# DC_Link.net
KiCad netlist of a schematic drawn in Altium Designer
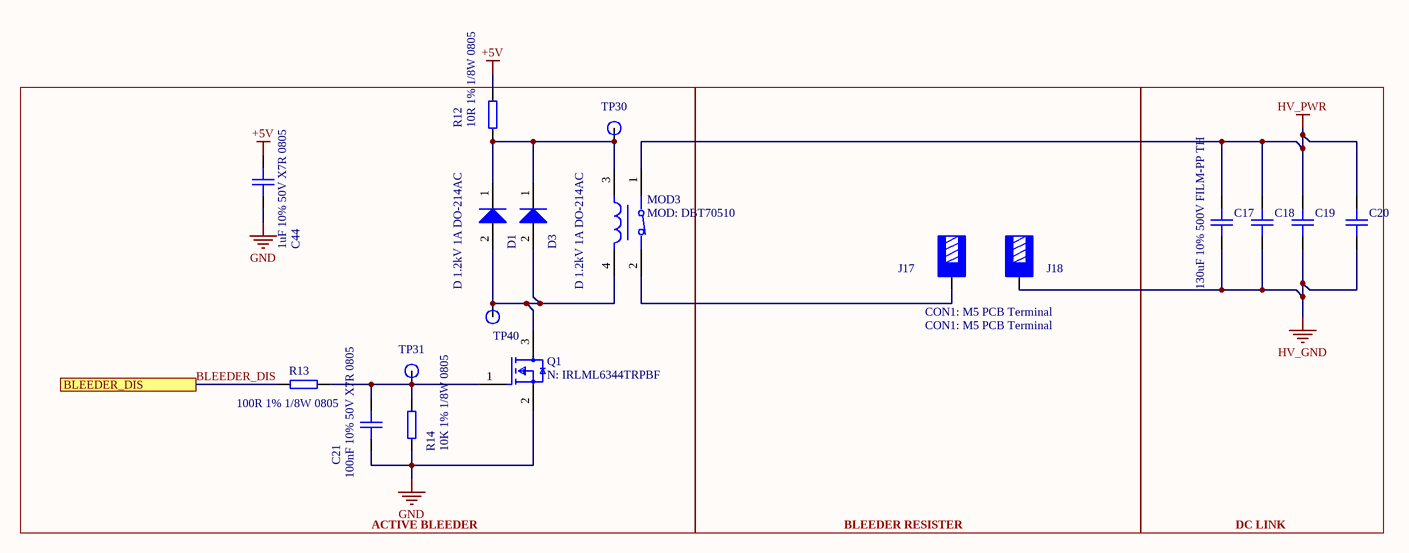
[diagram p0: DC_Link.SchDoc]

(export (version "E")
  (design (tool "Eeschema 10.0.6"))
  (components
    (comp (ref "C17")
      (value "130uF 10% 500V FILM-PP TH")
      (footprint "New footprint 1")
      (description "130 µF Film Capacitor 500V Polypropylene (PP), Metallized Radial - 4 Leads")
      (fields
        (field (name "MANUFACTURER") "KEMET")
        (field (name "MANUFACTURER PART NUMBER") "C4AQLBW6130A3NK")
      )
      (libsource (lib "EMEA- E-Tech Racing- I'Escola d'Enginyeria de Barcelona Est") (part "Copy of Capacitor_Non-Polarized"))
    )
    (comp (ref "C18")
      (value "130uF 10% 500V FILM-PP TH")
      (footprint "New footprint 1")
      (description "130 µF Film Capacitor 500V Polypropylene (PP), Metallized Radial - 4 Leads")
      (fields
        (field (name "MANUFACTURER") "KEMET")
        (field (name "MANUFACTURER PART NUMBER") "C4AQLBW6130A3NK")
      )
      (libsource (lib "EMEA- E-Tech Racing- I'Escola d'Enginyeria de Barcelona Est") (part "Copy of Capacitor_Non-Polarized"))
    )
    (comp (ref "C19")
      (value "130uF 10% 500V FILM-PP TH")
      (footprint "New footprint 1")
      (description "130 µF Film Capacitor 500V Polypropylene (PP), Metallized Radial - 4 Leads")
      (fields
        (field (name "MANUFACTURER") "KEMET")
        (field (name "MANUFACTURER PART NUMBER") "C4AQLBW6130A3NK")
      )
      (libsource (lib "EMEA- E-Tech Racing- I'Escola d'Enginyeria de Barcelona Est") (part "Copy of Capacitor_Non-Polarized"))
    )
    (comp (ref "C20")
      (value "130uF 10% 500V FILM-PP TH")
      (footprint "New footprint 1")
      (description "130 µF Film Capacitor 500V Polypropylene (PP), Metallized Radial - 4 Leads")
      (fields
        (field (name "MANUFACTURER") "KEMET")
        (field (name "MANUFACTURER PART NUMBER") "C4AQLBW6130A3NK")
      )
      (libsource (lib "EMEA- E-Tech Racing- I'Escola d'Enginyeria de Barcelona Est") (part "Copy of Capacitor_Non-Polarized"))
    )
    (comp (ref "C21")
      (value "100nF 10% 50V X7R 0805")
      (footprint "CAPC2012X10N")
      (description "Multilayer Ceramic Capacitors MLCC - SMD/SMT 50V 0.1uF X7R 0805 10%")
      (fields
        (field (name "MANUFACTURER") "Stackpole Electronics")
        (field (name "MANUFACTURER PART NUMBER") "CML0805X7R104KT50V")
      )
      (libsource (lib "EMEA- E-Tech Racing- I'Escola d'Enginyeria de Barcelona Est") (part "100nF 10% 50V X7R 0805-Symbol-1"))
    )
    (comp (ref "C44")
      (value "1uF 10% 50V X7R 0805")
      (footprint "CAPC2012X10N")
      (fields
        (field (name "MANUFACTURER PART NUMBER") "C2012X7R1H105K125AB")
        (field (name "MANUFACTURER") "TDK")
      )
      (libsource (lib "EMEA- E-Tech Racing- I'Escola d'Enginyeria de Barcelona Est") (part "68pF 10 630V C0G 0805"))
    )
    (comp (ref "D1")
      (value "D 1.2kV 1A DO-214AC")
      (footprint "FP-95400-MFG")
      (description "Rectifier Diode, 1 Phase, 1 Element, 1A, 1000V V(RRM), Silicon, DO-214AC")
      (fields (field (name "VOLTAGE") "1kV") (field (name "MANUFACTURER") "Vishay"))
      (libsource (lib "EMEA- E-Tech Racing- I'Escola d'Enginyeria de Barcelona Est") (part "SD 1.2kV 1A"))
    )
    (comp (ref "D3")
      (value "D 1.2kV 1A DO-214AC")
      (footprint "FP-95400-MFG")
      (description "Rectifier Diode, 1 Phase, 1 Element, 1A, 1000V V(RRM), Silicon, DO-214AC")
      (fields (field (name "VOLTAGE") "1kV") (field (name "MANUFACTURER") "Vishay"))
      (libsource (lib "EMEA- E-Tech Racing- I'Escola d'Enginyeria de Barcelona Est") (part "SD 1.2kV 1A"))
    )
    (comp (ref "J17")
      (value "CON1: M5 PCB Terminal")
      (footprint "CON1: M5 PCB Terminal-Footprint-1")
      (fields (field (name "MANUFACTURER") "Lab") (field (name "MANUFACTURER PART NUMBER") "M5 PCB Terminal"))
      (libsource (lib "EMEA- E-Tech Racing- I'Escola d'Enginyeria de Barcelona Est") (part "CON1{colon} M5 PCB Terminal-Symbol-1"))
    )
    (comp (ref "J18")
      (value "CON1: M5 PCB Terminal")
      (footprint "CON1: M5 PCB Terminal-Footprint-1")
      (fields (field (name "MANUFACTURER") "Lab") (field (name "MANUFACTURER PART NUMBER") "M5 PCB Terminal"))
      (libsource (lib "EMEA- E-Tech Racing- I'Escola d'Enginyeria de Barcelona Est") (part "CON1{colon} M5 PCB Terminal-Symbol-1"))
    )
    (comp (ref "MOD3")
      (value "MOD: DBT70510")
      (footprint "FP-DBT70510-MFG")
      (description "Electromechanical Relay SPST-NC 2A 5VDC 38Ohm Through Hole")
      (fields
        (field (name "MANUFACTURER") "Sensata /Cynergy3")
        (field (name "MANUFACTURER PART NUMBER") "DBT70510")
      )
      (libsource (lib "EMEA- E-Tech Racing- I'Escola d'Enginyeria de Barcelona Est") (part "27fd6d89efc3e5a8881bc064f812bb4"))
    )
    (comp (ref "Q1")
      (value "N: IRLML6344TRPBF")
      (footprint "FP-SOT23-MFG")
      (description "N-Channel 30 V 5A (Ta) 1.3W (Ta) Surface Mount Micro3™/SOT-23")
      (fields
        (field (name "MANUFACTURER PART NUMBER") "IRLML6344TRPBF")
        (field (name "MANUFACTURER") "Infineon")
      )
      (libsource (lib "EMEA- E-Tech Racing- I'Escola d'Enginyeria de Barcelona Est") (part "N{colon} IRLML6344TRPBF-Symbol-1"))
    )
    (comp (ref "R12")
      (value "10R 1% 1/8W 0805")
      (footprint "RESC2012X05N")
      (description "Res Thick Film 0805 10 Ohm 1% 0.125W ±100ppm/°C Molded SMD Paper T/R")
      (fields (field (name "TOLERANCE") "1%") (field (name "MANUFACTURER PART NUMBER") "RMCF0805FT10R0"))
      (libsource (lib "EMEA- E-Tech Racing- I'Escola d'Enginyeria de Barcelona Est") (part "100R 1 1/8W 0805"))
    )
    (comp (ref "R13")
      (value "100R 1% 1/8W 0805")
      (footprint "RESC2012X05N")
      (description "Res Thick Film 0805 100 Ohm 1% 0.125W ±100ppm/°C Molded SMD Paper T/R")
      (fields (field (name "TOLERANCE") "1%") (field (name "MANUFACTURER PART NUMBER") "RMCF0805FT100R"))
      (libsource (lib "EMEA- E-Tech Racing- I'Escola d'Enginyeria de Barcelona Est") (part "100R 1 1/8W 0805"))
    )
    (comp (ref "R14")
      (value "10K 1% 1/8W 0805")
      (footprint "RESC2012X05N")
      (description "Res Thick Film 0805 10K Ohm 1% 0.125W ±100ppm/°C Molded SMD Paper T/R")
      (fields (field (name "TOLERANCE") "1%") (field (name "MANUFACTURER PART NUMBER") "RMCF0805FT10K0"))
      (libsource (lib "EMEA- E-Tech Racing- I'Escola d'Enginyeria de Barcelona Est") (part "100R 1 1/8W 0805"))
    )
    (comp (ref "TP30")
      (value "TestPoint")
      (footprint "Test Point-Footprint-1")
      (libsource (lib "EMEA- E-Tech Racing- I'Escola d'Enginyeria de Barcelona Est") (part "New symbol 1"))
    )
    (comp (ref "TP31")
      (value "TestPoint")
      (footprint "Test Point-Footprint-1")
      (libsource (lib "EMEA- E-Tech Racing- I'Escola d'Enginyeria de Barcelona Est") (part "New symbol 1"))
    )
    (comp (ref "TP40")
      (value "TestPoint")
      (footprint "Test Point-Footprint-1")
      (libsource (lib "EMEA- E-Tech Racing- I'Escola d'Enginyeria de Barcelona Est") (part "New symbol 1"))
    )
  )
  (nets
    (net (code "1") (name "+5V") (class "Default")
      (node (ref "C44") (pin "2") (pinfunction "2_2") (pintype "passive"))
      (node (ref "R12") (pin "1") (pinfunction "1_1") (pintype "passive"))
    )
    (net (code "2") (name "/BLEEDER_DIS") (class "Default")
      (node (ref "R13") (pin "1") (pinfunction "1_1") (pintype "passive"))
    )
    (net (code "3") (name "GND") (class "Default")
      (node (ref "C21") (pin "1") (pinfunction "1_1") (pintype "passive"))
      (node (ref "C44") (pin "1") (pinfunction "1_1") (pintype "passive"))
      (node (ref "Q1") (pin "2") (pinfunction "S_2") (pintype "passive"))
      (node (ref "R14") (pin "1") (pinfunction "1_1") (pintype "passive"))
    )
    (net (code "4") (name "HV_GND") (class "Default")
      (node (ref "C17") (pin "1") (pinfunction "1_1") (pintype "passive"))
      (node (ref "C18") (pin "1") (pinfunction "1_1") (pintype "passive"))
      (node (ref "C19") (pin "1") (pinfunction "1_1") (pintype "passive"))
      (node (ref "C20") (pin "1") (pinfunction "1_1") (pintype "passive"))
      (node (ref "J18") (pin "1") (pinfunction "1_1") (pintype "passive"))
    )
    (net (code "5") (name "HV_PWR") (class "Default")
      (node (ref "C17") (pin "2") (pinfunction "2_2") (pintype "passive"))
      (node (ref "C18") (pin "2") (pinfunction "2_2") (pintype "passive"))
      (node (ref "C19") (pin "2") (pinfunction "2_2") (pintype "passive"))
      (node (ref "C20") (pin "2") (pinfunction "2_2") (pintype "passive"))
      (node (ref "MOD3") (pin "1") (pinfunction "1_1") (pintype "passive"))
    )
    (net (code "6") (name "Net-(D1-A)") (class "Default")
      (node (ref "D1") (pin "2") (pinfunction "A_2") (pintype "passive"))
      (node (ref "D3") (pin "2") (pinfunction "A_2") (pintype "passive"))
      (node (ref "MOD3") (pin "4") (pinfunction "+_4") (pintype "passive"))
      (node (ref "Q1") (pin "3") (pinfunction "D_3") (pintype "passive"))
      (node (ref "TP40") (pin "1") (pinfunction "1_1") (pintype "passive"))
    )
    (net (code "7") (name "Net-(D1-K)") (class "Default")
      (node (ref "D1") (pin "1") (pinfunction "K_1") (pintype "passive"))
      (node (ref "D3") (pin "1") (pinfunction "K_1") (pintype "passive"))
      (node (ref "MOD3") (pin "3") (pinfunction "-_3") (pintype "passive"))
      (node (ref "R12") (pin "2") (pinfunction "2_2") (pintype "passive"))
      (node (ref "TP30") (pin "1") (pinfunction "1_1") (pintype "passive"))
    )
    (net (code "8") (name "Net-(J17-Pad1)") (class "Default")
      (node (ref "J17") (pin "1") (pinfunction "1_1") (pintype "passive"))
      (node (ref "MOD3") (pin "2") (pinfunction "2_2") (pintype "passive"))
    )
    (net (code "9") (name "Net-(Q1-G)") (class "Default")
      (node (ref "C21") (pin "2") (pinfunction "2_2") (pintype "passive"))
      (node (ref "Q1") (pin "1") (pinfunction "G_1") (pintype "passive"))
      (node (ref "R13") (pin "2") (pinfunction "2_2") (pintype "passive"))
      (node (ref "R14") (pin "2") (pinfunction "2_2") (pintype "passive"))
      (node (ref "TP31") (pin "1") (pinfunction "1_1") (pintype "passive"))
    )
  )
)
